# ds1.net
KiCad netlist of a schematic drawn in EAGLE
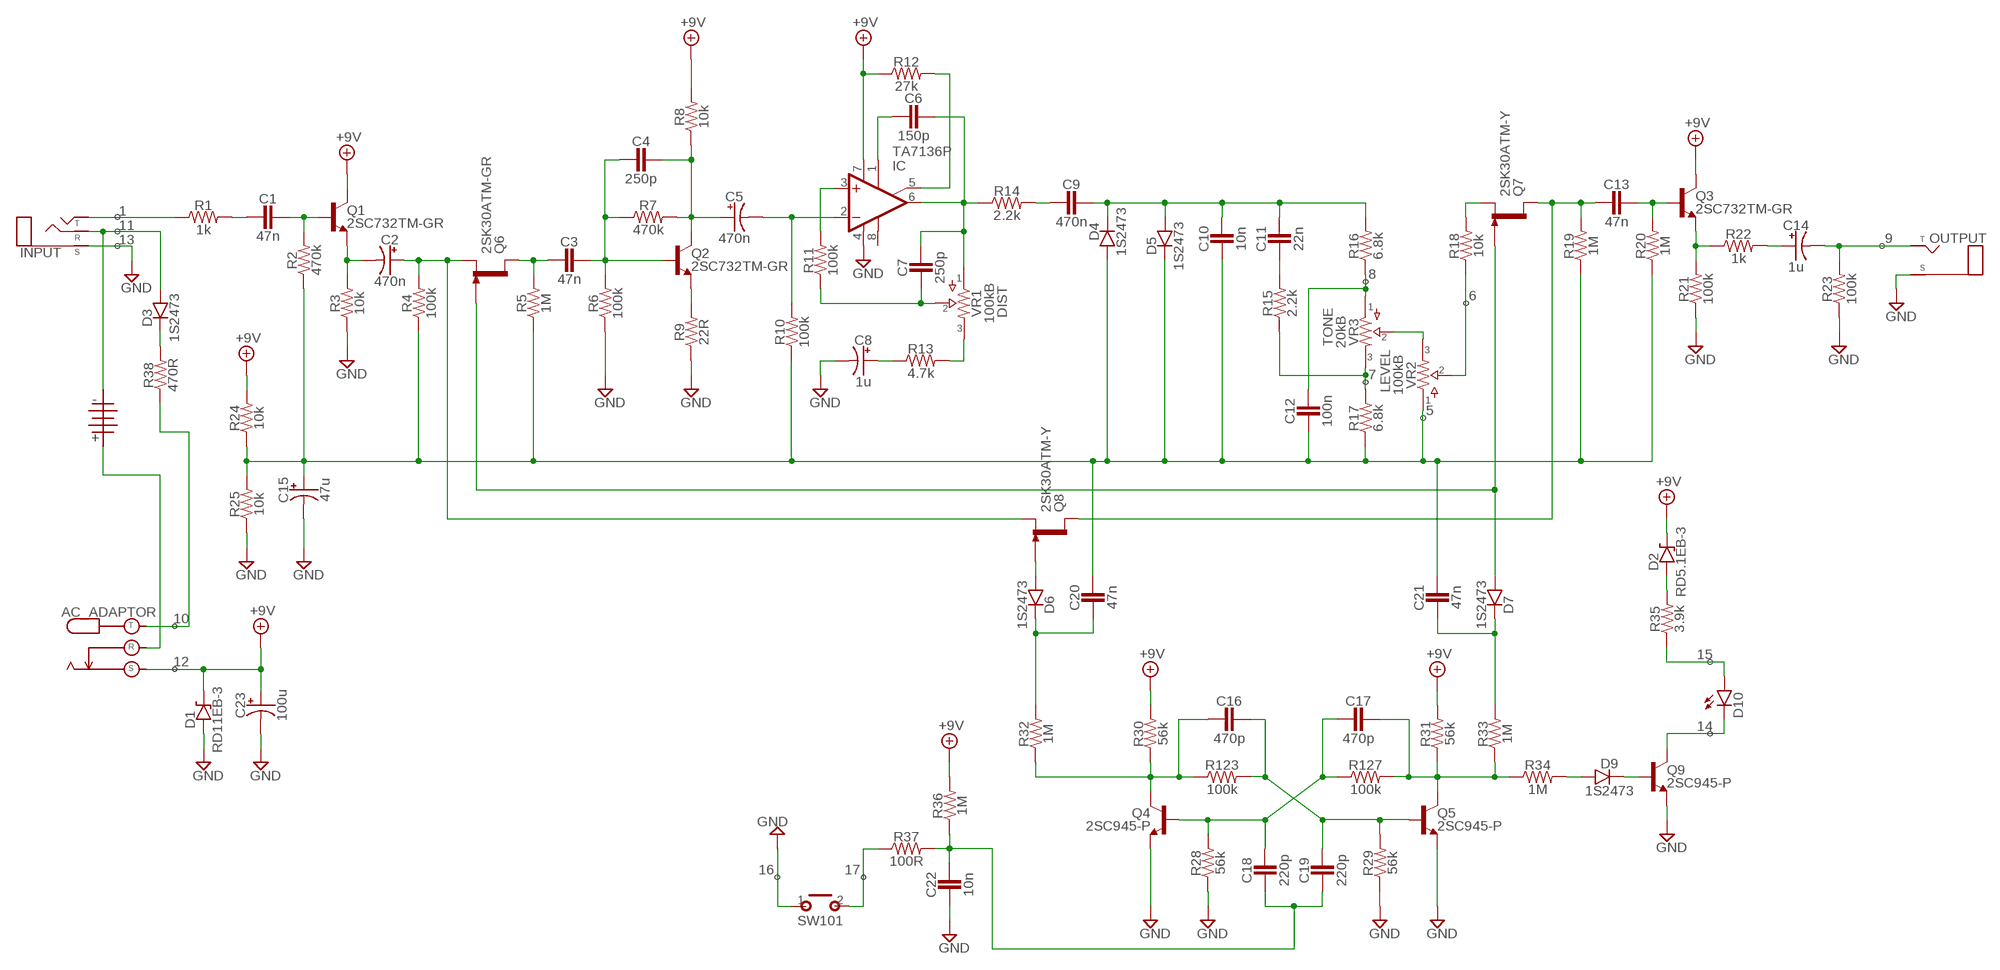
[diagram p0: schematic, sheet 1]

(export (version "E")
  (design (tool "Eeschema 10.0.6"))
  (components
    (comp (ref "1101")
      (value "BATTERY")
      (footprint "eagle-import:TWO_PADS")
      (libsource (lib "eagle-import") (part "BATTERY"))
    )
    (comp (ref "AC_ADAPTOR")
      (value "DC_KOBICONN")
      (footprint "eagle-import:DC_KOBICONN")
      (libsource (lib "eagle-import") (part "DC_KOBICONN"))
    )
    (comp (ref "C1")
      (value "47n")
      (footprint "eagle-import:BOX_SMALL")
      (libsource (lib "eagle-import") (part "CER/FILMBOX.1"))
    )
    (comp (ref "C2")
      (value "470n")
      (footprint "eagle-import:040_020")
      (libsource (lib "eagle-import") (part "0400"))
    )
    (comp (ref "C3")
      (value "47n")
      (footprint "eagle-import:BOX_SMALL")
      (libsource (lib "eagle-import") (part "CER/FILMBOX.1"))
    )
    (comp (ref "C4")
      (value "250p")
      (footprint "eagle-import:BOX_SMALL")
      (libsource (lib "eagle-import") (part "CER/FILMBOX.1"))
    )
    (comp (ref "C5")
      (value "470n")
      (footprint "eagle-import:040_020")
      (libsource (lib "eagle-import") (part "0400"))
    )
    (comp (ref "C6")
      (value "150p")
      (footprint "eagle-import:BOX_SMALL")
      (libsource (lib "eagle-import") (part "CER/FILMBOX.1"))
    )
    (comp (ref "C7")
      (value "250p")
      (footprint "eagle-import:BOX_SMALL")
      (libsource (lib "eagle-import") (part "CER/FILMBOX.1"))
    )
    (comp (ref "C8")
      (value "1u")
      (footprint "eagle-import:040_020")
      (libsource (lib "eagle-import") (part "0400"))
    )
    (comp (ref "C9")
      (value "470n")
      (footprint "eagle-import:BOX_SMALL")
      (libsource (lib "eagle-import") (part "CER/FILMBOX.1"))
    )
    (comp (ref "C10")
      (value "10n")
      (footprint "eagle-import:BOX_SMALL")
      (libsource (lib "eagle-import") (part "CER/FILMBOX.1"))
    )
    (comp (ref "C11")
      (value "22n")
      (footprint "eagle-import:BOX_SMALL")
      (libsource (lib "eagle-import") (part "CER/FILMBOX.1"))
    )
    (comp (ref "C12")
      (value "100n")
      (footprint "eagle-import:BOX_SMALL")
      (libsource (lib "eagle-import") (part "CER/FILMBOX.1"))
    )
    (comp (ref "C13")
      (value "47n")
      (footprint "eagle-import:BOX_SMALL")
      (libsource (lib "eagle-import") (part "CER/FILMBOX.1"))
    )
    (comp (ref "C14")
      (value "1u")
      (footprint "eagle-import:040_020")
      (libsource (lib "eagle-import") (part "0400"))
    )
    (comp (ref "C15")
      (value "47u")
      (footprint "eagle-import:040_020")
      (libsource (lib "eagle-import") (part "0400"))
    )
    (comp (ref "C16")
      (value "470p")
      (footprint "eagle-import:BOX_SMALL")
      (libsource (lib "eagle-import") (part "CER/FILMBOX.1"))
    )
    (comp (ref "C17")
      (value "470p")
      (footprint "eagle-import:BOX_SMALL")
      (libsource (lib "eagle-import") (part "CER/FILMBOX.1"))
    )
    (comp (ref "C18")
      (value "220p")
      (footprint "eagle-import:BOX_SMALL")
      (libsource (lib "eagle-import") (part "CER/FILMBOX.1"))
    )
    (comp (ref "C19")
      (value "220p")
      (footprint "eagle-import:BOX_SMALL")
      (libsource (lib "eagle-import") (part "CER/FILMBOX.1"))
    )
    (comp (ref "C20")
      (value "47n")
      (footprint "eagle-import:BOX_SMALL")
      (libsource (lib "eagle-import") (part "CER/FILMBOX.1"))
    )
    (comp (ref "C21")
      (value "47n")
      (footprint "eagle-import:BOX_SMALL")
      (libsource (lib "eagle-import") (part "CER/FILMBOX.1"))
    )
    (comp (ref "C22")
      (value "10n")
      (footprint "eagle-import:BOX_SMALL")
      (libsource (lib "eagle-import") (part "CER/FILMBOX.1"))
    )
    (comp (ref "C23")
      (value "100u")
      (footprint "eagle-import:040_020")
      (libsource (lib "eagle-import") (part "0400"))
    )
    (comp (ref "D1")
      (value "RD11EB-3")
      (footprint "eagle-import:DO41-2")
      (libsource (lib "eagle-import") (part "ZENER.2"))
    )
    (comp (ref "D2")
      (value "RD5.1EB-3")
      (footprint "eagle-import:DO41-2")
      (libsource (lib "eagle-import") (part "ZENER.2"))
    )
    (comp (ref "D3")
      (value "1S2473")
      (footprint "eagle-import:DO35-2")
      (libsource (lib "eagle-import") (part "DO35.2"))
    )
    (comp (ref "D4")
      (value "1S2473")
      (footprint "eagle-import:DO35-2")
      (libsource (lib "eagle-import") (part "DO35.2"))
    )
    (comp (ref "D5")
      (value "1S2473")
      (footprint "eagle-import:DO35-2")
      (libsource (lib "eagle-import") (part "DO35.2"))
    )
    (comp (ref "D6")
      (value "1S2473")
      (footprint "eagle-import:DO35-2")
      (libsource (lib "eagle-import") (part "DO35.2"))
    )
    (comp (ref "D7")
      (value "1S2473")
      (footprint "eagle-import:DO35-2")
      (libsource (lib "eagle-import") (part "DO35.2"))
    )
    (comp (ref "D9")
      (value "1S2473")
      (footprint "eagle-import:DO35-2")
      (libsource (lib "eagle-import") (part "DO35.2"))
    )
    (comp (ref "D10")
      (value "SLP1358")
      (footprint "eagle-import:3MM_D")
      (libsource (lib "eagle-import") (part "LED"))
    )
    (comp (ref "IC")
      (value "TA7136P")
      (footprint "eagle-import:DIL0")
      (libsource (lib "eagle-import") (part "SINGLETH"))
    )
    (comp (ref "INPUT")
      (value "STEREO3PADS")
      (footprint "eagle-import:THREEPADS")
      (libsource (lib "eagle-import") (part "STEREO3PADS"))
    )
    (comp (ref "OUTPUT")
      (value "MONO")
      (footprint "eagle-import:TWO_PADS")
      (libsource (lib "eagle-import") (part "MONO"))
    )
    (comp (ref "Q1")
      (value "2SC732TM-GR")
      (footprint "eagle-import:TO92-")
      (libsource (lib "eagle-import") (part "2SC828A"))
    )
    (comp (ref "Q2")
      (value "2SC732TM-GR")
      (footprint "eagle-import:TO92-")
      (libsource (lib "eagle-import") (part "2SC828A"))
    )
    (comp (ref "Q3")
      (value "2SC732TM-GR")
      (footprint "eagle-import:TO92-")
      (libsource (lib "eagle-import") (part "2SC828A"))
    )
    (comp (ref "Q4")
      (value "2SC945-P")
      (footprint "eagle-import:TO92-")
      (libsource (lib "eagle-import") (part "2SC828A"))
    )
    (comp (ref "Q5")
      (value "2SC945-P")
      (footprint "eagle-import:TO92-")
      (libsource (lib "eagle-import") (part "2SC828A"))
    )
    (comp (ref "Q6")
      (value "2SK30ATM-GR")
      (footprint "eagle-import:TO92-")
      (libsource (lib "eagle-import") (part "2N3819TO-92S"))
    )
    (comp (ref "Q7")
      (value "2SK30ATM-Y")
      (footprint "eagle-import:TO92-")
      (libsource (lib "eagle-import") (part "2N3819TO-92S"))
    )
    (comp (ref "Q8")
      (value "2SK30ATM-Y")
      (footprint "eagle-import:TO92-")
      (libsource (lib "eagle-import") (part "2N3819TO-92S"))
    )
    (comp (ref "Q9")
      (value "2SC945-P")
      (footprint "eagle-import:TO92-")
      (libsource (lib "eagle-import") (part "2SC828A"))
    )
    (comp (ref "R1")
      (value "1k")
      (footprint "eagle-import:R0207_3")
      (libsource (lib "eagle-import") (part "R_.3B"))
    )
    (comp (ref "R2")
      (value "470k")
      (footprint "eagle-import:R0207_3")
      (libsource (lib "eagle-import") (part "R_.3B"))
    )
    (comp (ref "R3")
      (value "10k")
      (footprint "eagle-import:R0207_3")
      (libsource (lib "eagle-import") (part "R_.3B"))
    )
    (comp (ref "R4")
      (value "100k")
      (footprint "eagle-import:R0207_3")
      (libsource (lib "eagle-import") (part "R_.3B"))
    )
    (comp (ref "R5")
      (value "1M")
      (footprint "eagle-import:R0207_3")
      (libsource (lib "eagle-import") (part "R_.3B"))
    )
    (comp (ref "R6")
      (value "100k")
      (footprint "eagle-import:R0207_3")
      (libsource (lib "eagle-import") (part "R_.3B"))
    )
    (comp (ref "R7")
      (value "470k")
      (footprint "eagle-import:R0207_3")
      (libsource (lib "eagle-import") (part "R_.3B"))
    )
    (comp (ref "R8")
      (value "10k")
      (footprint "eagle-import:R0207_3")
      (libsource (lib "eagle-import") (part "R_.3B"))
    )
    (comp (ref "R9")
      (value "22R")
      (footprint "eagle-import:R0207_3")
      (libsource (lib "eagle-import") (part "R_.3B"))
    )
    (comp (ref "R10")
      (value "100k")
      (footprint "eagle-import:R0207_3")
      (libsource (lib "eagle-import") (part "R_.3B"))
    )
    (comp (ref "R11")
      (value "100k")
      (footprint "eagle-import:R0207_3")
      (libsource (lib "eagle-import") (part "R_.3B"))
    )
    (comp (ref "R12")
      (value "27k")
      (footprint "eagle-import:R0207_3")
      (libsource (lib "eagle-import") (part "R_.3B"))
    )
    (comp (ref "R13")
      (value "4.7k")
      (footprint "eagle-import:R0207_3")
      (libsource (lib "eagle-import") (part "R_.3B"))
    )
    (comp (ref "R14")
      (value "2.2k")
      (footprint "eagle-import:R0207_3")
      (libsource (lib "eagle-import") (part "R_.3B"))
    )
    (comp (ref "R15")
      (value "2.2k")
      (footprint "eagle-import:R0207_3")
      (libsource (lib "eagle-import") (part "R_.3B"))
    )
    (comp (ref "R16")
      (value "6.8k")
      (footprint "eagle-import:R0207_3")
      (libsource (lib "eagle-import") (part "R_.3B"))
    )
    (comp (ref "R17")
      (value "6.8k")
      (footprint "eagle-import:R0207_3")
      (libsource (lib "eagle-import") (part "R_.3B"))
    )
    (comp (ref "R18")
      (value "10k")
      (footprint "eagle-import:R0207_3")
      (libsource (lib "eagle-import") (part "R_.3B"))
    )
    (comp (ref "R19")
      (value "1M")
      (footprint "eagle-import:R0207_3")
      (libsource (lib "eagle-import") (part "R_.3B"))
    )
    (comp (ref "R20")
      (value "1M")
      (footprint "eagle-import:R0207_3")
      (libsource (lib "eagle-import") (part "R_.3B"))
    )
    (comp (ref "R21")
      (value "100k")
      (footprint "eagle-import:R0207_3")
      (libsource (lib "eagle-import") (part "R_.3B"))
    )
    (comp (ref "R22")
      (value "1k")
      (footprint "eagle-import:R0207_3")
      (libsource (lib "eagle-import") (part "R_.3B"))
    )
    (comp (ref "R23")
      (value "100k")
      (footprint "eagle-import:R0207_3")
      (libsource (lib "eagle-import") (part "R_.3B"))
    )
    (comp (ref "R24")
      (value "10k")
      (footprint "eagle-import:R0207_3")
      (libsource (lib "eagle-import") (part "R_.3B"))
    )
    (comp (ref "R25")
      (value "10k")
      (footprint "eagle-import:R0207_3")
      (libsource (lib "eagle-import") (part "R_.3B"))
    )
    (comp (ref "R28")
      (value "56k")
      (footprint "eagle-import:R0207_3")
      (libsource (lib "eagle-import") (part "R_.3B"))
    )
    (comp (ref "R29")
      (value "56k")
      (footprint "eagle-import:R0207_3")
      (libsource (lib "eagle-import") (part "R_.3B"))
    )
    (comp (ref "R30")
      (value "56k")
      (footprint "eagle-import:R0207_3")
      (libsource (lib "eagle-import") (part "R_.3B"))
    )
    (comp (ref "R31")
      (value "56k")
      (footprint "eagle-import:R0207_3")
      (libsource (lib "eagle-import") (part "R_.3B"))
    )
    (comp (ref "R32")
      (value "1M")
      (footprint "eagle-import:R0207_3")
      (libsource (lib "eagle-import") (part "R_.3B"))
    )
    (comp (ref "R33")
      (value "1M")
      (footprint "eagle-import:R0207_3")
      (libsource (lib "eagle-import") (part "R_.3B"))
    )
    (comp (ref "R34")
      (value "1M")
      (footprint "eagle-import:R0207_3")
      (libsource (lib "eagle-import") (part "R_.3B"))
    )
    (comp (ref "R35")
      (value "3.9k")
      (footprint "eagle-import:R0207_3")
      (libsource (lib "eagle-import") (part "R_.3B"))
    )
    (comp (ref "R36")
      (value "1M")
      (footprint "eagle-import:R0207_3")
      (libsource (lib "eagle-import") (part "R_.3B"))
    )
    (comp (ref "R37")
      (value "100R")
      (footprint "eagle-import:R0207_3")
      (libsource (lib "eagle-import") (part "R_.3B"))
    )
    (comp (ref "R38")
      (value "470R")
      (footprint "eagle-import:R0207_3")
      (libsource (lib "eagle-import") (part "R_.3B"))
    )
    (comp (ref "R123")
      (value "100k")
      (footprint "eagle-import:R0207_3")
      (libsource (lib "eagle-import") (part "R_.3B"))
    )
    (comp (ref "R127")
      (value "100k")
      (footprint "eagle-import:R0207_3")
      (libsource (lib "eagle-import") (part "R_.3B"))
    )
    (comp (ref "SW101")
      (value "MOMENTARY")
      (footprint "eagle-import:SPST")
      (libsource (lib "eagle-import") (part "MOMENTARY"))
    )
    (comp (ref "VR1")
      (value "100kB")
      (footprint "eagle-import:16MM")
      (libsource (lib "eagle-import") (part "POTS16MM"))
    )
    (comp (ref "VR2")
      (value "100kB")
      (footprint "eagle-import:16MM")
      (libsource (lib "eagle-import") (part "POTS16MM"))
    )
    (comp (ref "VR3")
      (value "20kB")
      (footprint "eagle-import:16MM")
      (libsource (lib "eagle-import") (part "POTS16MM"))
    )
  )
  (nets
    (net (code "1") (name "+9V") (class "Default")
      (node (ref "AC_ADAPTOR") (pin "S") (pinfunction "S_S") (pintype "bidirectional"))
      (node (ref "C23") (pin "+") (pinfunction "+_+") (pintype "passive"))
      (node (ref "D1") (pin "C") (pinfunction "C_C") (pintype "passive"))
      (node (ref "D2") (pin "C") (pinfunction "C_C") (pintype "passive"))
      (node (ref "IC") (pin "7") (pinfunction "V+_7") (pintype "power_in"))
      (node (ref "Q1") (pin "2") (pinfunction "C_2") (pintype "passive"))
      (node (ref "Q3") (pin "2") (pinfunction "C_2") (pintype "passive"))
      (node (ref "R12") (pin "1") (pinfunction "1_1") (pintype "passive"))
      (node (ref "R24") (pin "2") (pinfunction "2_2") (pintype "passive"))
      (node (ref "R30") (pin "2") (pinfunction "2_2") (pintype "passive"))
      (node (ref "R31") (pin "2") (pinfunction "2_2") (pintype "passive"))
      (node (ref "R36") (pin "2") (pinfunction "2_2") (pintype "passive"))
      (node (ref "R8") (pin "2") (pinfunction "2_2") (pintype "passive"))
    )
    (net (code "2") (name "GND") (class "Default")
      (node (ref "C15") (pin "-") (pinfunction "-_-") (pintype "passive"))
      (node (ref "C22") (pin "2") (pinfunction "2_2") (pintype "passive"))
      (node (ref "C23") (pin "-") (pinfunction "-_-") (pintype "passive"))
      (node (ref "C8") (pin "-") (pinfunction "-_-") (pintype "passive"))
      (node (ref "D1") (pin "A") (pinfunction "A_A") (pintype "passive"))
      (node (ref "IC") (pin "4") (pinfunction "V-_4") (pintype "power_in"))
      (node (ref "INPUT") (pin "SLEEVE") (pinfunction "S_SLEEVE") (pintype "passive"))
      (node (ref "OUTPUT") (pin "S") (pinfunction "SLEEVE_S") (pintype "passive"))
      (node (ref "Q4") (pin "3") (pinfunction "E_3") (pintype "passive"))
      (node (ref "Q5") (pin "3") (pinfunction "E_3") (pintype "passive"))
      (node (ref "Q9") (pin "3") (pinfunction "E_3") (pintype "passive"))
      (node (ref "R21") (pin "1") (pinfunction "1_1") (pintype "passive"))
      (node (ref "R23") (pin "1") (pinfunction "1_1") (pintype "passive"))
      (node (ref "R25") (pin "1") (pinfunction "1_1") (pintype "passive"))
      (node (ref "R28") (pin "1") (pinfunction "1_1") (pintype "passive"))
      (node (ref "R29") (pin "1") (pinfunction "1_1") (pintype "passive"))
      (node (ref "R3") (pin "1") (pinfunction "1_1") (pintype "passive"))
      (node (ref "R6") (pin "1") (pinfunction "1_1") (pintype "passive"))
      (node (ref "R9") (pin "1") (pinfunction "1_1") (pintype "passive"))
      (node (ref "SW101") (pin "1") (pinfunction "P_1") (pintype "passive"))
    )
    (net (code "3") (name "Net-(1101-P$1)") (class "Default")
      (node (ref "1101") (pin "T") (pinfunction "P$1_T") (pintype "bidirectional"))
      (node (ref "AC_ADAPTOR") (pin "R") (pinfunction "R_R") (pintype "bidirectional"))
    )
    (net (code "4") (name "Net-(1101-P$2)") (class "Default")
      (node (ref "1101") (pin "S") (pinfunction "P$2_S") (pintype "bidirectional"))
      (node (ref "D3") (pin "A") (pinfunction "A_A") (pintype "passive"))
      (node (ref "INPUT") (pin "RING") (pinfunction "R_RING") (pintype "passive"))
    )
    (net (code "5") (name "Net-(AC_ADAPTOR-PadT)") (class "Default")
      (node (ref "AC_ADAPTOR") (pin "T") (pinfunction "T_T") (pintype "bidirectional"))
      (node (ref "R38") (pin "1") (pinfunction "1_1") (pintype "passive"))
    )
    (net (code "6") (name "Net-(C1-Pad2)") (class "Default")
      (node (ref "C1") (pin "2") (pinfunction "2_2") (pintype "passive"))
      (node (ref "R1") (pin "2") (pinfunction "2_2") (pintype "passive"))
    )
    (net (code "7") (name "Net-(C7-Pad2)") (class "Default")
      (node (ref "C7") (pin "2") (pinfunction "2_2") (pintype "passive"))
      (node (ref "R11") (pin "1") (pinfunction "1_1") (pintype "passive"))
      (node (ref "VR1") (pin "2") (pinfunction "2_2") (pintype "passive"))
    )
    (net (code "8") (name "Net-(C8-Pad+)") (class "Default")
      (node (ref "C8") (pin "+") (pinfunction "+_+") (pintype "passive"))
      (node (ref "R13") (pin "1") (pinfunction "1_1") (pintype "passive"))
    )
    (net (code "9") (name "Net-(C9-Pad2)") (class "Default")
      (node (ref "C9") (pin "2") (pinfunction "2_2") (pintype "passive"))
      (node (ref "R14") (pin "2") (pinfunction "2_2") (pintype "passive"))
    )
    (net (code "10") (name "Net-(C10-Pad1)") (class "Default")
      (node (ref "C10") (pin "1") (pinfunction "1_1") (pintype "passive"))
      (node (ref "C11") (pin "1") (pinfunction "1_1") (pintype "passive"))
      (node (ref "C9") (pin "1") (pinfunction "1_1") (pintype "passive"))
      (node (ref "D4") (pin "C") (pinfunction "C_C") (pintype "passive"))
      (node (ref "D5") (pin "A") (pinfunction "A_A") (pintype "passive"))
      (node (ref "R16") (pin "2") (pinfunction "2_2") (pintype "passive"))
    )
    (net (code "11") (name "Net-(C10-Pad2)") (class "Default")
      (node (ref "C10") (pin "2") (pinfunction "2_2") (pintype "passive"))
      (node (ref "C12") (pin "2") (pinfunction "2_2") (pintype "passive"))
      (node (ref "C15") (pin "+") (pinfunction "+_+") (pintype "passive"))
      (node (ref "C20") (pin "1") (pinfunction "1_1") (pintype "passive"))
      (node (ref "C21") (pin "1") (pinfunction "1_1") (pintype "passive"))
      (node (ref "D4") (pin "A") (pinfunction "A_A") (pintype "passive"))
      (node (ref "D5") (pin "C") (pinfunction "C_C") (pintype "passive"))
      (node (ref "R10") (pin "1") (pinfunction "1_1") (pintype "passive"))
      (node (ref "R17") (pin "1") (pinfunction "1_1") (pintype "passive"))
      (node (ref "R19") (pin "1") (pinfunction "1_1") (pintype "passive"))
      (node (ref "R2") (pin "1") (pinfunction "1_1") (pintype "passive"))
      (node (ref "R20") (pin "1") (pinfunction "1_1") (pintype "passive"))
      (node (ref "R24") (pin "1") (pinfunction "1_1") (pintype "passive"))
      (node (ref "R25") (pin "2") (pinfunction "2_2") (pintype "passive"))
      (node (ref "R4") (pin "1") (pinfunction "1_1") (pintype "passive"))
      (node (ref "R5") (pin "1") (pinfunction "1_1") (pintype "passive"))
      (node (ref "VR2") (pin "1") (pinfunction "1_1") (pintype "passive"))
    )
    (net (code "12") (name "Net-(C11-Pad2)") (class "Default")
      (node (ref "C11") (pin "2") (pinfunction "2_2") (pintype "passive"))
      (node (ref "R15") (pin "2") (pinfunction "2_2") (pintype "passive"))
    )
    (net (code "13") (name "Net-(C12-Pad1)") (class "Default")
      (node (ref "C12") (pin "1") (pinfunction "1_1") (pintype "passive"))
      (node (ref "R16") (pin "1") (pinfunction "1_1") (pintype "passive"))
      (node (ref "VR3") (pin "1") (pinfunction "1_1") (pintype "passive"))
    )
    (net (code "14") (name "Net-(C14-Pad+)") (class "Default")
      (node (ref "C14") (pin "+") (pinfunction "+_+") (pintype "passive"))
      (node (ref "R22") (pin "2") (pinfunction "2_2") (pintype "passive"))
    )
    (net (code "15") (name "Net-(C18-Pad2)") (class "Default")
      (node (ref "C18") (pin "2") (pinfunction "2_2") (pintype "passive"))
      (node (ref "C19") (pin "2") (pinfunction "2_2") (pintype "passive"))
      (node (ref "C22") (pin "1") (pinfunction "1_1") (pintype "passive"))
      (node (ref "R36") (pin "1") (pinfunction "1_1") (pintype "passive"))
      (node (ref "R37") (pin "2") (pinfunction "2_2") (pintype "passive"))
    )
    (net (code "16") (name "Net-(C20-Pad2)") (class "Default")
      (node (ref "C20") (pin "2") (pinfunction "2_2") (pintype "passive"))
      (node (ref "D6") (pin "C") (pinfunction "C_C") (pintype "passive"))
      (node (ref "R32") (pin "2") (pinfunction "2_2") (pintype "passive"))
    )
    (net (code "17") (name "Net-(C21-Pad2)") (class "Default")
      (node (ref "C21") (pin "2") (pinfunction "2_2") (pintype "passive"))
      (node (ref "D7") (pin "C") (pinfunction "C_C") (pintype "passive"))
      (node (ref "R33") (pin "2") (pinfunction "2_2") (pintype "passive"))
    )
    (net (code "18") (name "Net-(D2-PadA)") (class "Default")
      (node (ref "D2") (pin "A") (pinfunction "A_A") (pintype "passive"))
      (node (ref "R35") (pin "2") (pinfunction "2_2") (pintype "passive"))
    )
    (net (code "19") (name "Net-(D3-PadC)") (class "Default")
      (node (ref "D3") (pin "C") (pinfunction "C_C") (pintype "passive"))
      (node (ref "R38") (pin "2") (pinfunction "2_2") (pintype "passive"))
    )
    (net (code "20") (name "Net-(D9-PadA)") (class "Default")
      (node (ref "D9") (pin "A") (pinfunction "A_A") (pintype "passive"))
      (node (ref "R34") (pin "2") (pinfunction "2_2") (pintype "passive"))
    )
    (net (code "21") (name "Net-(D10-A)") (class "Default")
      (node (ref "D10") (pin "ANODE") (pinfunction "A_ANODE") (pintype "passive"))
      (node (ref "R35") (pin "1") (pinfunction "1_1") (pintype "passive"))
    )
    (net (code "22") (name "Net-(D10-C)") (class "Default")
      (node (ref "D10") (pin "P$1") (pinfunction "C_P$1") (pintype "passive"))
      (node (ref "Q9") (pin "2") (pinfunction "C_2") (pintype "passive"))
    )
    (net (code "23") (name "Net-(IC-+IN)") (class "Default")
      (node (ref "IC") (pin "3") (pinfunction "+IN_3") (pintype "input"))
      (node (ref "R11") (pin "2") (pinfunction "2_2") (pintype "passive"))
    )
    (net (code "24") (name "Net-(IC--IN)") (class "Default")
      (node (ref "C5") (pin "-") (pinfunction "-_-") (pintype "passive"))
      (node (ref "IC") (pin "2") (pinfunction "-IN_2") (pintype "input"))
      (node (ref "R10") (pin "2") (pinfunction "2_2") (pintype "passive"))
    )
    (net (code "25") (name "Net-(IC-ON1)") (class "Default")
      (node (ref "C6") (pin "2") (pinfunction "2_2") (pintype "passive"))
      (node (ref "IC") (pin "1") (pinfunction "ON1_1") (pintype "passive"))
    )
    (net (code "26") (name "Net-(IC-ON2)") (class "Default")
      (node (ref "IC") (pin "5") (pinfunction "ON2_5") (pintype "passive"))
      (node (ref "R12") (pin "2") (pinfunction "2_2") (pintype "passive"))
    )
    (net (code "27") (name "Net-(IC-OUT)") (class "Default")
      (node (ref "C6") (pin "1") (pinfunction "1_1") (pintype "passive"))
      (node (ref "C7") (pin "1") (pinfunction "1_1") (pintype "passive"))
      (node (ref "IC") (pin "6") (pinfunction "OUT_6") (pintype "output"))
      (node (ref "R14") (pin "1") (pinfunction "1_1") (pintype "passive"))
      (node (ref "VR1") (pin "1") (pinfunction "1_1") (pintype "passive"))
    )
    (net (code "28") (name "Net-(INPUT-T)") (class "Default")
      (node (ref "INPUT") (pin "TIP") (pinfunction "T_TIP") (pintype "passive"))
      (node (ref "R1") (pin "1") (pinfunction "1_1") (pintype "passive"))
    )
    (net (code "29") (name "Net-(OUTPUT-TIP)") (class "Default")
      (node (ref "C14") (pin "-") (pinfunction "-_-") (pintype "passive"))
      (node (ref "OUTPUT") (pin "T") (pinfunction "TIP_T") (pintype "passive"))
      (node (ref "R23") (pin "2") (pinfunction "2_2") (pintype "passive"))
    )
    (net (code "30") (name "Net-(Q1-B)") (class "Default")
      (node (ref "C1") (pin "1") (pinfunction "1_1") (pintype "passive"))
      (node (ref "Q1") (pin "1") (pinfunction "B_1") (pintype "passive"))
      (node (ref "R2") (pin "2") (pinfunction "2_2") (pintype "passive"))
    )
    (net (code "31") (name "Net-(Q1-E)") (class "Default")
      (node (ref "C2") (pin "-") (pinfunction "-_-") (pintype "passive"))
      (node (ref "Q1") (pin "3") (pinfunction "E_3") (pintype "passive"))
      (node (ref "R3") (pin "2") (pinfunction "2_2") (pintype "passive"))
    )
    (net (code "32") (name "Net-(Q2-B)") (class "Default")
      (node (ref "C3") (pin "1") (pinfunction "1_1") (pintype "passive"))
      (node (ref "C4") (pin "2") (pinfunction "2_2") (pintype "passive"))
      (node (ref "Q2") (pin "1") (pinfunction "B_1") (pintype "passive"))
      (node (ref "R6") (pin "2") (pinfunction "2_2") (pintype "passive"))
      (node (ref "R7") (pin "1") (pinfunction "1_1") (pintype "passive"))
    )
    (net (code "33") (name "Net-(Q2-C)") (class "Default")
      (node (ref "C4") (pin "1") (pinfunction "1_1") (pintype "passive"))
      (node (ref "C5") (pin "+") (pinfunction "+_+") (pintype "passive"))
      (node (ref "Q2") (pin "2") (pinfunction "C_2") (pintype "passive"))
      (node (ref "R7") (pin "2") (pinfunction "2_2") (pintype "passive"))
      (node (ref "R8") (pin "1") (pinfunction "1_1") (pintype "passive"))
    )
    (net (code "34") (name "Net-(Q2-E)") (class "Default")
      (node (ref "Q2") (pin "3") (pinfunction "E_3") (pintype "passive"))
      (node (ref "R9") (pin "2") (pinfunction "2_2") (pintype "passive"))
    )
    (net (code "35") (name "Net-(Q3-B)") (class "Default")
      (node (ref "C13") (pin "1") (pinfunction "1_1") (pintype "passive"))
      (node (ref "Q3") (pin "1") (pinfunction "B_1") (pintype "passive"))
      (node (ref "R20") (pin "2") (pinfunction "2_2") (pintype "passive"))
    )
    (net (code "36") (name "Net-(Q3-E)") (class "Default")
      (node (ref "Q3") (pin "3") (pinfunction "E_3") (pintype "passive"))
      (node (ref "R21") (pin "2") (pinfunction "2_2") (pintype "passive"))
      (node (ref "R22") (pin "1") (pinfunction "1_1") (pintype "passive"))
    )
    (net (code "37") (name "Net-(Q4-B)") (class "Default")
      (node (ref "C17") (pin "2") (pinfunction "2_2") (pintype "passive"))
      (node (ref "C18") (pin "1") (pinfunction "1_1") (pintype "passive"))
      (node (ref "Q4") (pin "1") (pinfunction "B_1") (pintype "passive"))
      (node (ref "R127") (pin "1") (pinfunction "1_1") (pintype "passive"))
      (node (ref "R28") (pin "2") (pinfunction "2_2") (pintype "passive"))
    )
    (net (code "38") (name "Net-(Q4-C)") (class "Default")
      (node (ref "C16") (pin "2") (pinfunction "2_2") (pintype "passive"))
      (node (ref "Q4") (pin "2") (pinfunction "C_2") (pintype "passive"))
      (node (ref "R123") (pin "1") (pinfunction "1_1") (pintype "passive"))
      (node (ref "R30") (pin "1") (pinfunction "1_1") (pintype "passive"))
      (node (ref "R32") (pin "1") (pinfunction "1_1") (pintype "passive"))
    )
    (net (code "39") (name "Net-(Q5-B)") (class "Default")
      (node (ref "C16") (pin "1") (pinfunction "1_1") (pintype "passive"))
      (node (ref "C19") (pin "1") (pinfunction "1_1") (pintype "passive"))
      (node (ref "Q5") (pin "1") (pinfunction "B_1") (pintype "passive"))
      (node (ref "R123") (pin "2") (pinfunction "2_2") (pintype "passive"))
      (node (ref "R29") (pin "2") (pinfunction "2_2") (pintype "passive"))
    )
    (net (code "40") (name "Net-(Q5-C)") (class "Default")
      (node (ref "C17") (pin "1") (pinfunction "1_1") (pintype "passive"))
      (node (ref "Q5") (pin "2") (pinfunction "C_2") (pintype "passive"))
      (node (ref "R127") (pin "2") (pinfunction "2_2") (pintype "passive"))
      (node (ref "R31") (pin "1") (pinfunction "1_1") (pintype "passive"))
      (node (ref "R33") (pin "1") (pinfunction "1_1") (pintype "passive"))
      (node (ref "R34") (pin "1") (pinfunction "1_1") (pintype "passive"))
    )
    (net (code "41") (name "Net-(Q6-D)") (class "Default")
      (node (ref "C3") (pin "2") (pinfunction "2_2") (pintype "passive"))
      (node (ref "Q6") (pin "3") (pinfunction "D_3") (pintype "passive"))
      (node (ref "R5") (pin "2") (pinfunction "2_2") (pintype "passive"))
    )
    (net (code "42") (name "Net-(Q6-G)") (class "Default")
      (node (ref "D7") (pin "A") (pinfunction "A_A") (pintype "passive"))
      (node (ref "Q6") (pin "2") (pinfunction "G_2") (pintype "passive"))
      (node (ref "Q7") (pin "2") (pinfunction "G_2") (pintype "passive"))
    )
    (net (code "43") (name "Net-(Q6-S)") (class "Default")
      (node (ref "C2") (pin "+") (pinfunction "+_+") (pintype "passive"))
      (node (ref "Q6") (pin "1") (pinfunction "S_1") (pintype "passive"))
      (node (ref "Q8") (pin "1") (pinfunction "S_1") (pintype "passive"))
      (node (ref "R4") (pin "2") (pinfunction "2_2") (pintype "passive"))
    )
    (net (code "44") (name "Net-(Q7-D)") (class "Default")
      (node (ref "C13") (pin "2") (pinfunction "2_2") (pintype "passive"))
      (node (ref "Q7") (pin "3") (pinfunction "D_3") (pintype "passive"))
      (node (ref "Q8") (pin "3") (pinfunction "D_3") (pintype "passive"))
      (node (ref "R19") (pin "2") (pinfunction "2_2") (pintype "passive"))
    )
    (net (code "45") (name "Net-(Q7-S)") (class "Default")
      (node (ref "Q7") (pin "1") (pinfunction "S_1") (pintype "passive"))
      (node (ref "R18") (pin "2") (pinfunction "2_2") (pintype "passive"))
    )
    (net (code "46") (name "Net-(Q8-G)") (class "Default")
      (node (ref "D6") (pin "A") (pinfunction "A_A") (pintype "passive"))
      (node (ref "Q8") (pin "2") (pinfunction "G_2") (pintype "passive"))
    )
    (net (code "47") (name "Net-(Q9-B)") (class "Default")
      (node (ref "D9") (pin "C") (pinfunction "C_C") (pintype "passive"))
      (node (ref "Q9") (pin "1") (pinfunction "B_1") (pintype "passive"))
    )
    (net (code "48") (name "Net-(R13-Pad2)") (class "Default")
      (node (ref "R13") (pin "2") (pinfunction "2_2") (pintype "passive"))
      (node (ref "VR1") (pin "3") (pinfunction "3_3") (pintype "passive"))
    )
    (net (code "49") (name "Net-(R15-Pad1)") (class "Default")
      (node (ref "R15") (pin "1") (pinfunction "1_1") (pintype "passive"))
      (node (ref "R17") (pin "2") (pinfunction "2_2") (pintype "passive"))
      (node (ref "VR3") (pin "3") (pinfunction "3_3") (pintype "passive"))
    )
    (net (code "50") (name "Net-(R18-Pad1)") (class "Default")
      (node (ref "R18") (pin "1") (pinfunction "1_1") (pintype "passive"))
      (node (ref "VR2") (pin "2") (pinfunction "2_2") (pintype "passive"))
    )
    (net (code "51") (name "Net-(SW101-S)") (class "Default")
      (node (ref "R37") (pin "1") (pinfunction "1_1") (pintype "passive"))
      (node (ref "SW101") (pin "2") (pinfunction "S_2") (pintype "passive"))
    )
    (net (code "52") (name "Net-(VR2-Pad3)") (class "Default")
      (node (ref "VR2") (pin "3") (pinfunction "3_3") (pintype "passive"))
      (node (ref "VR3") (pin "2") (pinfunction "2_2") (pintype "passive"))
    )
    (net (code "53") (name "unconnected-(IC-OPT-Pad8)") (class "Default")
      (node (ref "IC") (pin "8") (pinfunction "OPT_8") (pintype "passive"))
    )
  )
)
